# Modular_BO.net
KiCad netlist of a schematic drawn in Altium Designer
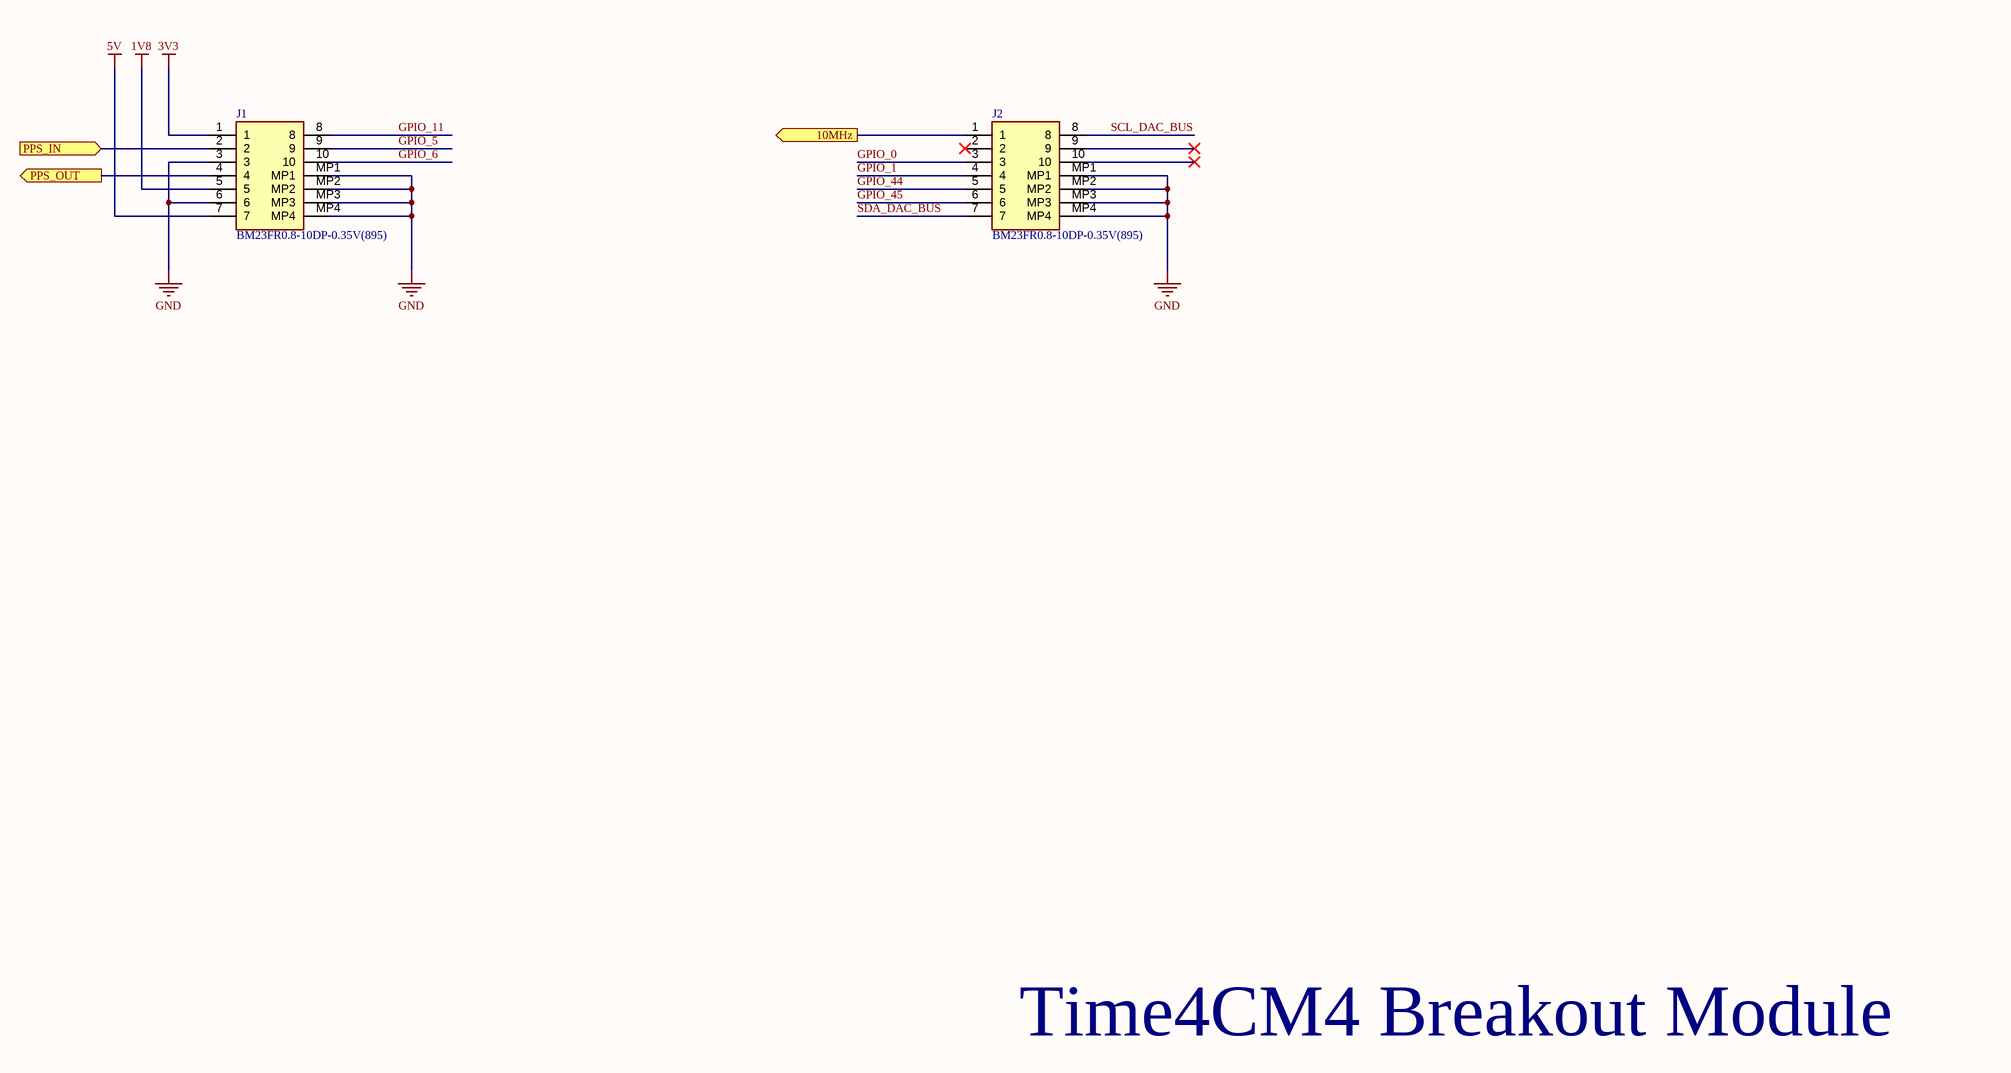
[diagram p0: Modular_BO.SchDoc]

(export (version "E")
  (design (tool "Eeschema 10.0.6"))
  (components
    (comp (ref "J1")
      (value "BM23FR0.8-10DP-0.35V(895)")
      (footprint "SamacSys:BM23FR0810DP035V895")
      (description "Connector")
      (fields
        (field (name "MANUFACTURER_PART_NUMBER") "BM23FR0.8-10DS-0.35V(895)")
        (field (name "MOUSER PART NUMBER") "798-3FR0810DS035V895")
      )
      (libsource (lib "*") (part "BM23FR0.8-10DS-0.35V_895_"))
    )
    (comp (ref "J2")
      (value "BM23FR0.8-10DP-0.35V(895)")
      (footprint "SamacSys:BM23FR0810DP035V895")
      (description "Connector")
      (fields
        (field (name "MANUFACTURER_PART_NUMBER") "BM23FR0.8-10DS-0.35V(895)")
        (field (name "MOUSER PART NUMBER") "798-3FR0810DS035V895")
      )
      (libsource (lib "*") (part "BM23FR0.8-10DS-0.35V_895_"))
    )
  )
  (nets
    (net (code "1") (name "/10MHz") (class "Default")
      (node (ref "J2") (pin "1") (pinfunction "1_1") (pintype "passive"))
    )
    (net (code "2") (name "/GPIO_0") (class "Default")
      (node (ref "J2") (pin "3") (pinfunction "3_3") (pintype "passive"))
    )
    (net (code "3") (name "/GPIO_1") (class "Default")
      (node (ref "J2") (pin "4") (pinfunction "4_4") (pintype "passive"))
    )
    (net (code "4") (name "/GPIO_5") (class "Default")
      (node (ref "J1") (pin "9") (pinfunction "9_9") (pintype "passive"))
    )
    (net (code "5") (name "/GPIO_6") (class "Default")
      (node (ref "J1") (pin "10") (pinfunction "10_10") (pintype "passive"))
    )
    (net (code "6") (name "/GPIO_11") (class "Default")
      (node (ref "J1") (pin "8") (pinfunction "8_8") (pintype "passive"))
    )
    (net (code "7") (name "/GPIO_44") (class "Default")
      (node (ref "J2") (pin "5") (pinfunction "5_5") (pintype "passive"))
    )
    (net (code "8") (name "/GPIO_45") (class "Default")
      (node (ref "J2") (pin "6") (pinfunction "6_6") (pintype "passive"))
    )
    (net (code "9") (name "/PPS_IN") (class "Default")
      (node (ref "J1") (pin "2") (pinfunction "2_2") (pintype "passive"))
    )
    (net (code "10") (name "/PPS_OUT") (class "Default")
      (node (ref "J1") (pin "4") (pinfunction "4_4") (pintype "passive"))
    )
    (net (code "11") (name "/SCL_DAC_BUS") (class "Default")
      (node (ref "J2") (pin "8") (pinfunction "8_8") (pintype "passive"))
    )
    (net (code "12") (name "/SDA_DAC_BUS") (class "Default")
      (node (ref "J2") (pin "7") (pinfunction "7_7") (pintype "passive"))
    )
    (net (code "13") (name "1V8") (class "Default")
      (node (ref "J1") (pin "5") (pinfunction "5_5") (pintype "passive"))
    )
    (net (code "14") (name "3V3") (class "Default")
      (node (ref "J1") (pin "1") (pinfunction "1_1") (pintype "passive"))
    )
    (net (code "15") (name "5V") (class "Default")
      (node (ref "J1") (pin "7") (pinfunction "7_7") (pintype "passive"))
    )
    (net (code "16") (name "GND") (class "Default")
      (node (ref "J1") (pin "3") (pinfunction "3_3") (pintype "passive"))
      (node (ref "J1") (pin "6") (pinfunction "6_6") (pintype "passive"))
      (node (ref "J1") (pin "MP1") (pinfunction "MP1_MP1") (pintype "passive"))
      (node (ref "J1") (pin "MP2") (pinfunction "MP2_MP2") (pintype "passive"))
      (node (ref "J1") (pin "MP3") (pinfunction "MP3_MP3") (pintype "passive"))
      (node (ref "J1") (pin "MP4") (pinfunction "MP4_MP4") (pintype "passive"))
      (node (ref "J2") (pin "MP1") (pinfunction "MP1_MP1") (pintype "passive"))
      (node (ref "J2") (pin "MP2") (pinfunction "MP2_MP2") (pintype "passive"))
      (node (ref "J2") (pin "MP3") (pinfunction "MP3_MP3") (pintype "passive"))
      (node (ref "J2") (pin "MP4") (pinfunction "MP4_MP4") (pintype "passive"))
    )
    (net (code "17") (name "unconnected-(J2-Pad2)") (class "Default")
      (node (ref "J2") (pin "2") (pinfunction "2_2") (pintype "passive+no_connect"))
    )
    (net (code "18") (name "unconnected-(J2-Pad9)") (class "Default")
      (node (ref "J2") (pin "9") (pinfunction "9_9") (pintype "passive+no_connect"))
    )
    (net (code "19") (name "unconnected-(J2-Pad10)") (class "Default")
      (node (ref "J2") (pin "10") (pinfunction "10_10") (pintype "passive+no_connect"))
    )
  )
)
